# Interfaces.net
KiCad netlist of a schematic drawn in Altium Designer
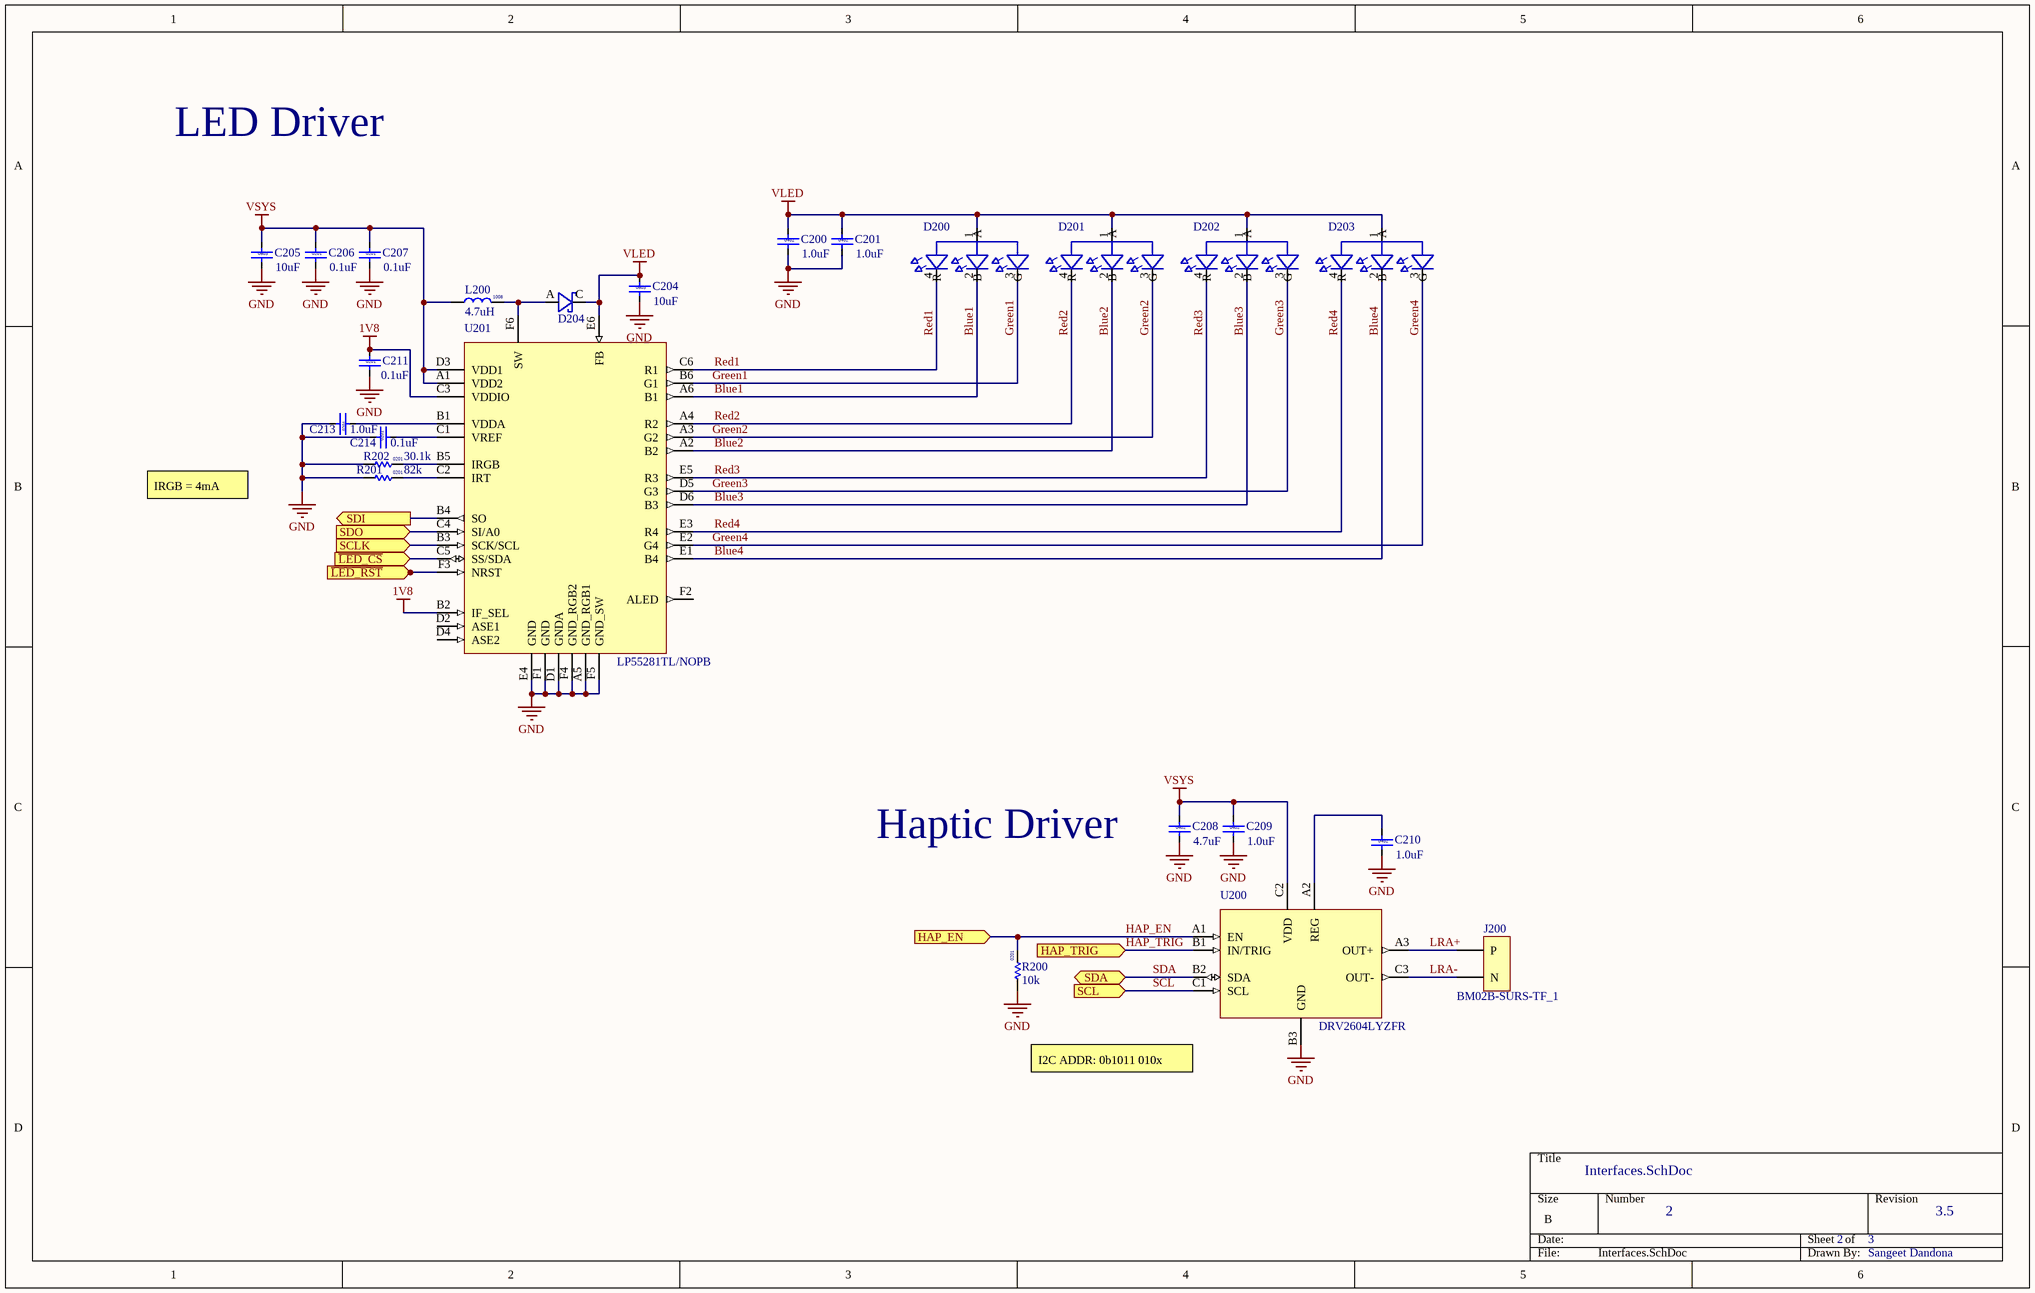
[diagram p0: Interfaces.SchDoc]

(export (version "E")
  (design (tool "Eeschema 10.0.6"))
  (components
    (comp (ref "C200")
      (value "1.0uF")
      (footprint "Cap 0402 HD")
      (description "CAP CER 1UF 10V 10% X5R 0402")
      (fields (field (name "SIZE") "0402") (field (name "MF") "Murata Electronics North America"))
      (libsource (lib "Rigado_AltiumLib") (part "Cap Chip"))
    )
    (comp (ref "C201")
      (value "1.0uF")
      (footprint "Cap 0402 HD")
      (description "CAP CER 1UF 10V 10% X5R 0402")
      (fields (field (name "SIZE") "0402") (field (name "MF") "Murata Electronics North America"))
      (libsource (lib "Rigado_AltiumLib") (part "Cap Chip"))
    )
    (comp (ref "C204")
      (value "10uF")
      (footprint "Cap 0603")
      (description "CAP CER 10UF 10V 20% X5R 0603")
      (fields (field (name "SIZE") "0603") (field (name "MF") "TDK Corporation"))
      (libsource (lib "Rigado_AltiumLib") (part "Cap Chip"))
    )
    (comp (ref "C205")
      (value "10uF")
      (footprint "Cap 0603")
      (description "CAP CER 10UF 10V 20% X5R 0603")
      (fields (field (name "SIZE") "0603") (field (name "MF") "TDK Corporation"))
      (libsource (lib "Rigado_AltiumLib") (part "Cap Chip"))
    )
    (comp (ref "C206")
      (value "0.1uF")
      (footprint "Cap 0201 HD")
      (description "CAP CER 0.1UF 6.3V 10% X5R 0201")
      (fields (field (name "SIZE") "0201") (field (name "MF") "Murata Electronics North America"))
      (libsource (lib "Rigado_AltiumLib") (part "Cap Chip"))
    )
    (comp (ref "C207")
      (value "0.1uF")
      (footprint "Cap 0201 HD")
      (description "CAP CER 0.1UF 6.3V 10% X5R 0201")
      (fields (field (name "SIZE") "0201") (field (name "MF") "Murata Electronics North America"))
      (libsource (lib "Rigado_AltiumLib") (part "Cap Chip"))
    )
    (comp (ref "C208")
      (value "4.7uF")
      (footprint "Cap 0402 HD")
      (description "CAP CER 4.7UF 10V 20% X5R 0402")
      (fields (field (name "SIZE") "0402") (field (name "MF") "Samsung Electro-Mechanics America, Inc."))
      (libsource (lib "Rigado_AltiumLib") (part "Cap Chip"))
    )
    (comp (ref "C209")
      (value "1.0uF")
      (footprint "Cap 0402 HD")
      (description "CAP CER 1UF 10V 10% X5R 0402")
      (fields (field (name "SIZE") "0402") (field (name "MF") "Murata Electronics North America"))
      (libsource (lib "Rigado_AltiumLib") (part "Cap Chip"))
    )
    (comp (ref "C210")
      (value "1.0uF")
      (footprint "Cap 0402 HD")
      (description "CAP CER 1UF 10V 10% X5R 0402")
      (fields (field (name "SIZE") "0402") (field (name "MF") "Murata Electronics North America"))
      (libsource (lib "Rigado_AltiumLib") (part "Cap Chip"))
    )
    (comp (ref "C211")
      (value "0.1uF")
      (footprint "Cap 0201 HD")
      (description "CAP CER 0.1UF 6.3V 10% X5R 0201")
      (fields (field (name "SIZE") "0201") (field (name "MF") "Murata Electronics North America"))
      (libsource (lib "Rigado_AltiumLib") (part "Cap Chip"))
    )
    (comp (ref "C213")
      (value "1.0uF")
      (footprint "Cap 0201 HD")
      (description "CAP CER 1UF 6.3V 20% X5R 0201")
      (fields (field (name "SIZE") "0201") (field (name "MF") "Samsung Electro-Mechanics America, Inc."))
      (libsource (lib "Rigado_AltiumLib") (part "Cap Chip"))
    )
    (comp (ref "C214")
      (value "0.1uF")
      (footprint "Cap 0201 HD")
      (description "CAP CER 0.1UF 6.3V 10% X5R 0201")
      (fields (field (name "SIZE") "0201") (field (name "MF") "Murata Electronics North America"))
      (libsource (lib "Rigado_AltiumLib") (part "Cap Chip"))
    )
    (comp (ref "D200")
      (value "~")
      (footprint "4-PLCC")
      (description "LED RGB 3-IN-1 SMD 4PLCC")
      (fields (field (name "MF") "Cree Inc."))
      (libsource (lib "Rigado_AltiumLib") (part "LED_RGB_CA_2"))
    )
    (comp (ref "D201")
      (value "~")
      (footprint "4-PLCC")
      (description "LED RGB 3-IN-1 SMD 4PLCC")
      (fields (field (name "MF") "Cree Inc."))
      (libsource (lib "Rigado_AltiumLib") (part "LED_RGB_CA_2"))
    )
    (comp (ref "D202")
      (value "~")
      (footprint "4-PLCC")
      (description "LED RGB 3-IN-1 SMD 4PLCC")
      (fields (field (name "MF") "Cree Inc."))
      (libsource (lib "Rigado_AltiumLib") (part "LED_RGB_CA_2"))
    )
    (comp (ref "D203")
      (value "~")
      (footprint "4-PLCC")
      (description "LED RGB 3-IN-1 SMD 4PLCC")
      (fields (field (name "MF") "Cree Inc."))
      (libsource (lib "Rigado_AltiumLib") (part "LED_RGB_CA_2"))
    )
    (comp (ref "D204")
      (value "~")
      (footprint "SOD-123F_U")
      (description "DIODE SCHOTTKY 20V 1A SOD123FL")
      (fields (field (name "MF") "ON Semiconductor"))
      (libsource (lib "LOCAL_Rigado_AltiumLib") (part "Diode_Schottky"))
    )
    (comp (ref "J200")
      (value "BM02B-SURS-TF_1")
      (footprint "BM02B-SURS-TF")
      (description "CONN HDR SUR TOP 2POS 0.8MM TIN")
      (fields (field (name "MF") "JST Sales America Inc."))
      (libsource (lib "JWB-001_Main") (part "BM02B-SURS-TF_1"))
    )
    (comp (ref "L200")
      (value "4.7uH")
      (footprint "IND 1008")
      (description "FIXED IND 4.7UH 1A 250 MOHM SMD")
      (fields (field (name "SIZE") "1008") (field (name "MF") "Samsung Electro-Mechanics America, Inc."))
      (libsource (lib "Rigado_AltiumLib") (part "Ind sm"))
    )
    (comp (ref "R200")
      (value "10k")
      (footprint "RES 0201 HD")
      (description "RES SMD 10K OHM 5% 1/20W 0201")
      (fields (field (name "SIZE") "0201") (field (name "MF") "Rohm Semiconductor"))
      (libsource (lib "Rigado_AltiumLib") (part "Res sm"))
    )
    (comp (ref "R201")
      (value "82k")
      (footprint "RES 0201 HD")
      (description "RES SMD 82K OHM 1% 1/20W 0201")
      (fields (field (name "SIZE") "0201") (field (name "MF") "Samsung Electro-Mechanics America, Inc."))
      (libsource (lib "Rigado_AltiumLib") (part "Res sm"))
    )
    (comp (ref "R202")
      (value "30.1k")
      (footprint "RES 0201 HD")
      (description "RES SMD 30.1K OHM 1% 1/20W 0201")
      (fields (field (name "SIZE") "0201") (field (name "MF") "Yageo"))
      (libsource (lib "Rigado_AltiumLib") (part "Res sm"))
    )
    (comp (ref "U200")
      (value "~")
      (footprint "BGA0.5P3x3-9Pin")
      (description "IC ERM/LRA HAPTIC DRIVER 9DSBGA")
      (fields (field (name "MF") "Texas Instruments") (field (name "MFPN") "DRV2604LYZFR"))
      (libsource (lib "Rigado_AltiumLib") (part "DRV2604L"))
    )
    (comp (ref "U201")
      (value "~")
      (footprint "BGA0.5P6x6-36Pin")
      (description "IC LED DRIVER RGLTR DIM 36USMD")
      (fields (field (name "MF") "Texas Instruments") (field (name "MFPN") "LP55281TL/NOPB"))
      (libsource (lib "Rigado_AltiumLib") (part "LP55281"))
    )
  )
  (nets
    (net (code "1") (name "/Blue1") (class "Default")
      (node (ref "D200") (pin "2") (pinfunction "B_2") (pintype "passive"))
      (node (ref "U201") (pin "A6") (pinfunction "B1_A6") (pintype "output"))
    )
    (net (code "2") (name "/Blue2") (class "Default")
      (node (ref "D201") (pin "2") (pinfunction "B_2") (pintype "passive"))
      (node (ref "U201") (pin "A2") (pinfunction "B2_A2") (pintype "output"))
    )
    (net (code "3") (name "/Blue3") (class "Default")
      (node (ref "D202") (pin "2") (pinfunction "B_2") (pintype "passive"))
      (node (ref "U201") (pin "D6") (pinfunction "B3_D6") (pintype "output"))
    )
    (net (code "4") (name "/Blue4") (class "Default")
      (node (ref "D203") (pin "2") (pinfunction "B_2") (pintype "passive"))
      (node (ref "U201") (pin "E1") (pinfunction "B4_E1") (pintype "output"))
    )
    (net (code "5") (name "/Green1") (class "Default")
      (node (ref "D200") (pin "3") (pinfunction "G_3") (pintype "passive"))
      (node (ref "U201") (pin "B6") (pinfunction "G1_B6") (pintype "output"))
    )
    (net (code "6") (name "/Green2") (class "Default")
      (node (ref "D201") (pin "3") (pinfunction "G_3") (pintype "passive"))
      (node (ref "U201") (pin "A3") (pinfunction "G2_A3") (pintype "output"))
    )
    (net (code "7") (name "/Green3") (class "Default")
      (node (ref "D202") (pin "3") (pinfunction "G_3") (pintype "passive"))
      (node (ref "U201") (pin "D5") (pinfunction "G3_D5") (pintype "output"))
    )
    (net (code "8") (name "/Green4") (class "Default")
      (node (ref "D203") (pin "3") (pinfunction "G_3") (pintype "passive"))
      (node (ref "U201") (pin "E2") (pinfunction "G4_E2") (pintype "output"))
    )
    (net (code "9") (name "/HAP_EN") (class "Default")
      (node (ref "R200") (pin "2") (pinfunction "2_2") (pintype "passive"))
      (node (ref "U200") (pin "A1") (pinfunction "EN_A1") (pintype "input"))
    )
    (net (code "10") (name "/HAP_TRIG") (class "Default")
      (node (ref "U200") (pin "B1") (pinfunction "IN/TRIG_B1") (pintype "input"))
    )
    (net (code "11") (name "/LED_CS") (class "Default")
      (node (ref "U201") (pin "C5") (pinfunction "SS/SDA_C5") (pintype "bidirectional"))
    )
    (net (code "12") (name "/LED_RST") (class "Default")
      (node (ref "U201") (pin "F3") (pinfunction "NRST_F3") (pintype "input"))
    )
    (net (code "13") (name "/LRA+") (class "Default")
      (node (ref "J200") (pin "1") (pinfunction "P_1") (pintype "passive"))
      (node (ref "U200") (pin "A3") (pinfunction "OUT+_A3") (pintype "output"))
    )
    (net (code "14") (name "/LRA-") (class "Default")
      (node (ref "J200") (pin "2") (pinfunction "N_2") (pintype "passive"))
      (node (ref "U200") (pin "C3") (pinfunction "OUT-_C3") (pintype "output"))
    )
    (net (code "15") (name "/Red1") (class "Default")
      (node (ref "D200") (pin "4") (pinfunction "R_4") (pintype "passive"))
      (node (ref "U201") (pin "C6") (pinfunction "R1_C6") (pintype "output"))
    )
    (net (code "16") (name "/Red2") (class "Default")
      (node (ref "D201") (pin "4") (pinfunction "R_4") (pintype "passive"))
      (node (ref "U201") (pin "A4") (pinfunction "R2_A4") (pintype "output"))
    )
    (net (code "17") (name "/Red3") (class "Default")
      (node (ref "D202") (pin "4") (pinfunction "R_4") (pintype "passive"))
      (node (ref "U201") (pin "E5") (pinfunction "R3_E5") (pintype "output"))
    )
    (net (code "18") (name "/Red4") (class "Default")
      (node (ref "D203") (pin "4") (pinfunction "R_4") (pintype "passive"))
      (node (ref "U201") (pin "E3") (pinfunction "R4_E3") (pintype "output"))
    )
    (net (code "19") (name "/SCL") (class "Default")
      (node (ref "U200") (pin "C1") (pinfunction "SCL_C1") (pintype "input"))
    )
    (net (code "20") (name "/SCLK") (class "Default")
      (node (ref "U201") (pin "B3") (pinfunction "SCK/SCL_B3") (pintype "input"))
    )
    (net (code "21") (name "/SDA") (class "Default")
      (node (ref "U200") (pin "B2") (pinfunction "SDA_B2") (pintype "bidirectional"))
    )
    (net (code "22") (name "/SDI") (class "Default")
      (node (ref "U201") (pin "B4") (pinfunction "SO_B4") (pintype "output"))
    )
    (net (code "23") (name "/SDO") (class "Default")
      (node (ref "U201") (pin "C4") (pinfunction "SI/A0_C4") (pintype "input"))
    )
    (net (code "24") (name "1V8") (class "Default")
      (node (ref "C211") (pin "1") (pinfunction "1_1") (pintype "passive"))
      (node (ref "U201") (pin "B2") (pinfunction "IF_SEL_B2") (pintype "input"))
      (node (ref "U201") (pin "C3") (pinfunction "VDDIO_C3") (pintype "power_in"))
    )
    (net (code "25") (name "GND") (class "Default")
      (node (ref "C200") (pin "2") (pinfunction "2_2") (pintype "passive"))
      (node (ref "C201") (pin "2") (pinfunction "2_2") (pintype "passive"))
      (node (ref "C204") (pin "2") (pinfunction "2_2") (pintype "passive"))
      (node (ref "C205") (pin "2") (pinfunction "2_2") (pintype "passive"))
      (node (ref "C206") (pin "2") (pinfunction "2_2") (pintype "passive"))
      (node (ref "C207") (pin "2") (pinfunction "2_2") (pintype "passive"))
      (node (ref "C208") (pin "2") (pinfunction "2_2") (pintype "passive"))
      (node (ref "C209") (pin "2") (pinfunction "2_2") (pintype "passive"))
      (node (ref "C210") (pin "2") (pinfunction "2_2") (pintype "passive"))
      (node (ref "C211") (pin "2") (pinfunction "2_2") (pintype "passive"))
      (node (ref "C213") (pin "2") (pinfunction "2_2") (pintype "passive"))
      (node (ref "C214") (pin "1") (pinfunction "1_1") (pintype "passive"))
      (node (ref "R200") (pin "1") (pinfunction "1_1") (pintype "passive"))
      (node (ref "R201") (pin "1") (pinfunction "1_1") (pintype "passive"))
      (node (ref "R202") (pin "1") (pinfunction "1_1") (pintype "passive"))
      (node (ref "U200") (pin "B3") (pinfunction "GND_B3") (pintype "power_in"))
      (node (ref "U201") (pin "A5") (pinfunction "GND_RGB1_A5") (pintype "power_in"))
      (node (ref "U201") (pin "D1") (pinfunction "GNDA_D1") (pintype "power_in"))
      (node (ref "U201") (pin "E4") (pinfunction "GND_E4") (pintype "power_in"))
      (node (ref "U201") (pin "F1") (pinfunction "GND_F1") (pintype "power_in"))
      (node (ref "U201") (pin "F4") (pinfunction "GND_RGB2_F4") (pintype "power_in"))
      (node (ref "U201") (pin "F5") (pinfunction "GND_SW_F5") (pintype "power_in"))
    )
    (net (code "26") (name "Net-(U200-REG)") (class "Default")
      (node (ref "C210") (pin "1") (pinfunction "1_1") (pintype "passive"))
      (node (ref "U200") (pin "A2") (pinfunction "REG_A2") (pintype "power_in"))
    )
    (net (code "27") (name "Net-(U201-IRGB)") (class "Default")
      (node (ref "R202") (pin "2") (pinfunction "2_2") (pintype "passive"))
      (node (ref "U201") (pin "B5") (pinfunction "IRGB_B5") (pintype "passive"))
    )
    (net (code "28") (name "Net-(U201-IRT)") (class "Default")
      (node (ref "R201") (pin "2") (pinfunction "2_2") (pintype "passive"))
      (node (ref "U201") (pin "C2") (pinfunction "IRT_C2") (pintype "passive"))
    )
    (net (code "29") (name "Net-(U201-SW)") (class "Default")
      (node (ref "D204") (pin "A") (pintype "passive"))
      (node (ref "L200") (pin "2") (pinfunction "2_2") (pintype "passive"))
      (node (ref "U201") (pin "F6") (pinfunction "SW_F6") (pintype "power_in"))
    )
    (net (code "30") (name "Net-(U201-VDDA)") (class "Default")
      (node (ref "C213") (pin "1") (pinfunction "1_1") (pintype "passive"))
      (node (ref "U201") (pin "B1") (pinfunction "VDDA_B1") (pintype "power_in"))
    )
    (net (code "31") (name "Net-(U201-VREF)") (class "Default")
      (node (ref "C214") (pin "2") (pinfunction "2_2") (pintype "passive"))
      (node (ref "U201") (pin "C1") (pinfunction "VREF_C1") (pintype "passive"))
    )
    (net (code "32") (name "VLED") (class "Default")
      (node (ref "C200") (pin "1") (pinfunction "1_1") (pintype "passive"))
      (node (ref "C201") (pin "1") (pinfunction "1_1") (pintype "passive"))
      (node (ref "C204") (pin "1") (pinfunction "1_1") (pintype "passive"))
      (node (ref "D200") (pin "1") (pinfunction "A_1") (pintype "passive"))
      (node (ref "D201") (pin "1") (pinfunction "A_1") (pintype "passive"))
      (node (ref "D202") (pin "1") (pinfunction "A_1") (pintype "passive"))
      (node (ref "D203") (pin "1") (pinfunction "A_1") (pintype "passive"))
      (node (ref "D204") (pin "C") (pintype "passive"))
      (node (ref "U201") (pin "E6") (pinfunction "FB_E6") (pintype "input"))
    )
    (net (code "33") (name "VSYS") (class "Default")
      (node (ref "C205") (pin "1") (pinfunction "1_1") (pintype "passive"))
      (node (ref "C206") (pin "1") (pinfunction "1_1") (pintype "passive"))
      (node (ref "C207") (pin "1") (pinfunction "1_1") (pintype "passive"))
      (node (ref "C208") (pin "1") (pinfunction "1_1") (pintype "passive"))
      (node (ref "C209") (pin "1") (pinfunction "1_1") (pintype "passive"))
      (node (ref "L200") (pin "1") (pinfunction "1_1") (pintype "passive"))
      (node (ref "U200") (pin "C2") (pinfunction "VDD_C2") (pintype "power_in"))
      (node (ref "U201") (pin "A1") (pinfunction "VDD2_A1") (pintype "power_in"))
      (node (ref "U201") (pin "D3") (pinfunction "VDD1_D3") (pintype "power_in"))
    )
    (net (code "34") (name "unconnected-(U201-ALED-PadF2)") (class "Default")
      (node (ref "U201") (pin "F2") (pinfunction "ALED_F2") (pintype "output"))
    )
    (net (code "35") (name "unconnected-(U201-ASE1-PadD2)") (class "Default")
      (node (ref "U201") (pin "D2") (pinfunction "ASE1_D2") (pintype "input"))
    )
    (net (code "36") (name "unconnected-(U201-ASE2-PadD4)") (class "Default")
      (node (ref "U201") (pin "D4") (pinfunction "ASE2_D4") (pintype "input"))
    )
  )
)
